# hdmi.net
KiCad netlist of a schematic drawn in Altium Designer
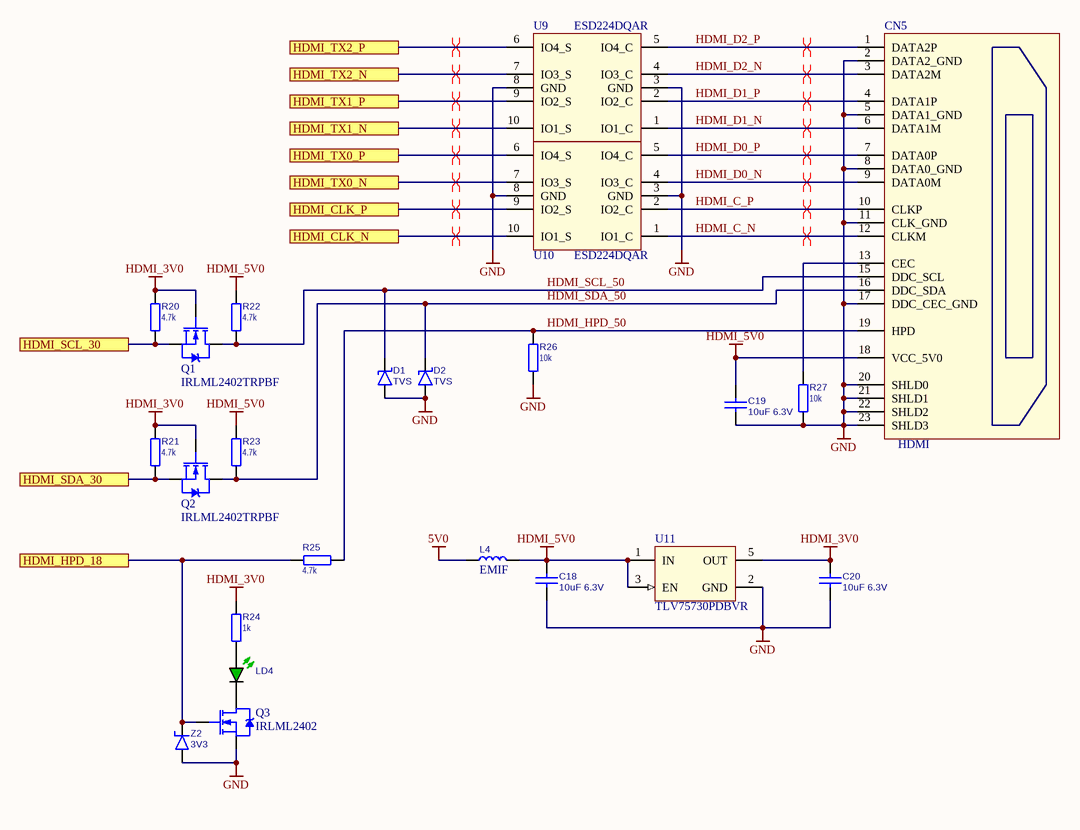
[diagram p0: hdmi.SchDoc]

(export (version "E")
  (design (tool "Eeschema 10.0.6"))
  (components
    (comp (ref "C18")
      (value "10uF 6.3V")
      (footprint "Capacitors:C0603")
      (description "CAP_NPOL")
      (fields (field (name "Comment") "CC0603MRX5R5BB106"))
      (libsource (lib "capacitors") (part "CAP_NPOL"))
    )
    (comp (ref "C19")
      (value "10uF 6.3V")
      (footprint "Capacitors:C0603")
      (description "CAP_NPOL")
      (fields (field (name "Comment") "CC0603MRX5R5BB106"))
      (libsource (lib "capacitors") (part "CAP_NPOL"))
    )
    (comp (ref "C20")
      (value "10uF 6.3V")
      (footprint "Capacitors:C0603")
      (description "CAP_NPOL")
      (fields (field (name "Comment") "CC0603MRX5R5BB106"))
      (libsource (lib "capacitors") (part "CAP_NPOL"))
    )
    (comp (ref "CN5")
      (value "HDMI")
      (footprint "1747981-1")
      (fields (field (name "Comment") "KLS1-285-19-22-N1B"))
      (libsource (lib "HDMI") (part "HDMI"))
    )
    (comp (ref "D1")
      (value "TVS")
      (footprint "SOD-323")
      (description "SHOTTKY")
      (fields (field (name "Comment") "CDSOD323-T05LC"))
      (libsource (lib "diodes") (part "SHOTTKY"))
    )
    (comp (ref "D2")
      (value "TVS")
      (footprint "SOD-323")
      (description "SHOTTKY")
      (fields (field (name "Comment") "CDSOD323-T05LC"))
      (libsource (lib "diodes") (part "SHOTTKY"))
    )
    (comp (ref "L4")
      (value "EMIF")
      (footprint "IND0805")
      (description "IND_WO_IRON")
      (fields (field (name "Comment") "BLM21PG221SN1D"))
      (libsource (lib "inductors") (part "IND_WO_IRON"))
    )
    (comp (ref "LD4")
      (value "LED_G")
      (footprint "LED0805")
      (description "LED Green")
      (libsource (lib "leds") (part "LED_GREEN"))
    )
    (comp (ref "Q1")
      (value "IRLML2402TRPBF")
      (footprint "SOT-23-3")
      (description "HEXFET Power MOSFET")
      (libsource (lib "MOSFET") (part "N-Channel"))
    )
    (comp (ref "Q2")
      (value "IRLML2402TRPBF")
      (footprint "SOT-23-3")
      (description "HEXFET Power MOSFET")
      (libsource (lib "MOSFET") (part "N-Channel"))
    )
    (comp (ref "Q3")
      (value "IRLML2402")
      (footprint "SOT-23-3")
      (description "HEXFET Power MOSFET")
      (libsource (lib "MOSFET") (part "N-Channel"))
    )
    (comp (ref "R20")
      (value "4.7k")
      (footprint "R0603")
      (description "RES")
      (libsource (lib "resistors") (part "RESISTOR"))
    )
    (comp (ref "R21")
      (value "4.7k")
      (footprint "R0603")
      (description "RES")
      (libsource (lib "resistors") (part "RESISTOR"))
    )
    (comp (ref "R22")
      (value "4.7k")
      (footprint "R0603")
      (description "RES")
      (libsource (lib "resistors") (part "RESISTOR"))
    )
    (comp (ref "R23")
      (value "4.7k")
      (footprint "R0603")
      (description "RES")
      (libsource (lib "resistors") (part "RESISTOR"))
    )
    (comp (ref "R24")
      (value "1k")
      (footprint "R0603")
      (description "RES")
      (libsource (lib "resistors") (part "RESISTOR"))
    )
    (comp (ref "R25")
      (value "4.7k")
      (footprint "R0603")
      (description "RES")
      (libsource (lib "resistors") (part "RESISTOR"))
    )
    (comp (ref "R26")
      (value "10k")
      (footprint "R0603")
      (description "RES")
      (libsource (lib "resistors") (part "RESISTOR"))
    )
    (comp (ref "R27")
      (value "10k")
      (footprint "R0603")
      (description "RES")
      (libsource (lib "resistors") (part "RESISTOR"))
    )
    (comp (ref "U9")
      (value "ESD224DQAR")
      (footprint "USON-10")
      (description "ESD224 Low Clamping 4-Channel ESD Protection Device for HDMI Interface")
      (libsource (lib "ESD") (part "ESD224"))
    )
    (comp (ref "U10")
      (value "ESD224DQAR")
      (footprint "USON-10")
      (description "ESD224 Low Clamping 4-Channel ESD Protection Device for HDMI Interface")
      (libsource (lib "ESD") (part "ESD224"))
    )
    (comp (ref "U11")
      (value "TLV75730PDBVR")
      (footprint "SOT-23-5")
      (description "Capacitor-Free, 300-mA, Low-Dropout Regulator with Foldback Current Limit for Portable Devices")
      (libsource (lib "TLV733P") (part "TLV733P"))
    )
    (comp (ref "Z2")
      (value "3V3")
      (footprint "SOD-80C")
      (description "ZENNER")
      (fields (field (name "Comment") "BZV55-C3V3.115"))
      (libsource (lib "diodes") (part "ZENNER_1"))
    )
  )
  (nets
    (net (code "1") (name "/HDMI_CLK_N") (class "Default")
      (node (ref "U10") (pin "10") (pinfunction "IO1_S_10") (pintype "passive"))
    )
    (net (code "2") (name "/HDMI_CLK_P") (class "Default")
      (node (ref "U10") (pin "9") (pinfunction "IO2_S_9") (pintype "passive"))
    )
    (net (code "3") (name "/HDMI_C_N") (class "Default")
      (node (ref "CN5") (pin "12") (pinfunction "CLKM_12") (pintype "passive"))
      (node (ref "U10") (pin "1") (pinfunction "IO1_C_1") (pintype "passive"))
    )
    (net (code "4") (name "/HDMI_C_P") (class "Default")
      (node (ref "CN5") (pin "10") (pinfunction "CLKP_10") (pintype "passive"))
      (node (ref "U10") (pin "2") (pinfunction "IO2_C_2") (pintype "passive"))
    )
    (net (code "5") (name "/HDMI_D0_N") (class "Default")
      (node (ref "CN5") (pin "9") (pinfunction "DATA0M_9") (pintype "passive"))
      (node (ref "U10") (pin "4") (pinfunction "IO3_C_4") (pintype "passive"))
    )
    (net (code "6") (name "/HDMI_D0_P") (class "Default")
      (node (ref "CN5") (pin "7") (pinfunction "DATA0P_7") (pintype "passive"))
      (node (ref "U10") (pin "5") (pinfunction "IO4_C_5") (pintype "passive"))
    )
    (net (code "7") (name "/HDMI_D1_N") (class "Default")
      (node (ref "CN5") (pin "6") (pinfunction "DATA1M_6") (pintype "passive"))
      (node (ref "U9") (pin "1") (pinfunction "IO1_C_1") (pintype "passive"))
    )
    (net (code "8") (name "/HDMI_D1_P") (class "Default")
      (node (ref "CN5") (pin "4") (pinfunction "DATA1P_4") (pintype "passive"))
      (node (ref "U9") (pin "2") (pinfunction "IO2_C_2") (pintype "passive"))
    )
    (net (code "9") (name "/HDMI_D2_N") (class "Default")
      (node (ref "CN5") (pin "3") (pinfunction "DATA2M_3") (pintype "passive"))
      (node (ref "U9") (pin "4") (pinfunction "IO3_C_4") (pintype "passive"))
    )
    (net (code "10") (name "/HDMI_D2_P") (class "Default")
      (node (ref "CN5") (pin "1") (pinfunction "DATA2P_1") (pintype "passive"))
      (node (ref "U9") (pin "5") (pinfunction "IO4_C_5") (pintype "passive"))
    )
    (net (code "11") (name "/HDMI_HPD_18") (class "Default")
      (node (ref "Q3") (pin "1") (pinfunction "G_1") (pintype "passive"))
      (node (ref "R25") (pin "1") (pinfunction "1_1") (pintype "passive"))
      (node (ref "Z2") (pin "2") (pinfunction "K_2") (pintype "passive"))
    )
    (net (code "12") (name "/HDMI_HPD_50") (class "Default")
      (node (ref "CN5") (pin "19") (pinfunction "HPD_19") (pintype "passive"))
      (node (ref "R25") (pin "2") (pinfunction "2_2") (pintype "passive"))
      (node (ref "R26") (pin "2") (pinfunction "2_2") (pintype "passive"))
    )
    (net (code "13") (name "/HDMI_SCL_30") (class "Default")
      (node (ref "Q1") (pin "2") (pinfunction "S_2") (pintype "passive"))
      (node (ref "R20") (pin "1") (pinfunction "1_1") (pintype "passive"))
    )
    (net (code "14") (name "/HDMI_SCL_50") (class "Default")
      (node (ref "CN5") (pin "15") (pinfunction "DDC_SCL_15") (pintype "passive"))
      (node (ref "D1") (pin "2") (pinfunction "K_2") (pintype "passive"))
      (node (ref "Q1") (pin "3") (pinfunction "D_3") (pintype "passive"))
      (node (ref "R22") (pin "1") (pinfunction "1_1") (pintype "passive"))
    )
    (net (code "15") (name "/HDMI_SDA_30") (class "Default")
      (node (ref "Q2") (pin "2") (pinfunction "S_2") (pintype "passive"))
      (node (ref "R21") (pin "1") (pinfunction "1_1") (pintype "passive"))
    )
    (net (code "16") (name "/HDMI_SDA_50") (class "Default")
      (node (ref "CN5") (pin "16") (pinfunction "DDC_SDA_16") (pintype "passive"))
      (node (ref "D2") (pin "2") (pinfunction "K_2") (pintype "passive"))
      (node (ref "Q2") (pin "3") (pinfunction "D_3") (pintype "passive"))
      (node (ref "R23") (pin "1") (pinfunction "1_1") (pintype "passive"))
    )
    (net (code "17") (name "/HDMI_TX0_N") (class "Default")
      (node (ref "U10") (pin "7") (pinfunction "IO3_S_7") (pintype "passive"))
    )
    (net (code "18") (name "/HDMI_TX0_P") (class "Default")
      (node (ref "U10") (pin "6") (pinfunction "IO4_S_6") (pintype "passive"))
    )
    (net (code "19") (name "/HDMI_TX1_N") (class "Default")
      (node (ref "U9") (pin "10") (pinfunction "IO1_S_10") (pintype "passive"))
    )
    (net (code "20") (name "/HDMI_TX1_P") (class "Default")
      (node (ref "U9") (pin "9") (pinfunction "IO2_S_9") (pintype "passive"))
    )
    (net (code "21") (name "/HDMI_TX2_N") (class "Default")
      (node (ref "U9") (pin "7") (pinfunction "IO3_S_7") (pintype "passive"))
    )
    (net (code "22") (name "/HDMI_TX2_P") (class "Default")
      (node (ref "U9") (pin "6") (pinfunction "IO4_S_6") (pintype "passive"))
    )
    (net (code "23") (name "5V0") (class "Default") (node (ref "L4") (pin "2") (pintype "passive")))
    (net (code "24") (name "GND") (class "Default")
      (node (ref "C18") (pin "2") (pinfunction "2_2") (pintype "passive"))
      (node (ref "C19") (pin "2") (pinfunction "2_2") (pintype "passive"))
      (node (ref "C20") (pin "2") (pinfunction "2_2") (pintype "passive"))
      (node (ref "CN5") (pin "11") (pinfunction "CLK_GND_11") (pintype "passive"))
      (node (ref "CN5") (pin "17") (pinfunction "DDC_CEC_GND_17") (pintype "passive"))
      (node (ref "CN5") (pin "2") (pinfunction "DATA2_GND_2") (pintype "passive"))
      (node (ref "CN5") (pin "20") (pinfunction "SHLD0_20") (pintype "passive"))
      (node (ref "CN5") (pin "21") (pinfunction "SHLD1_21") (pintype "passive"))
      (node (ref "CN5") (pin "22") (pinfunction "SHLD2_22") (pintype "passive"))
      (node (ref "CN5") (pin "23") (pinfunction "SHLD3_23") (pintype "passive"))
      (node (ref "CN5") (pin "5") (pinfunction "DATA1_GND_5") (pintype "passive"))
      (node (ref "CN5") (pin "8") (pinfunction "DATA0_GND_8") (pintype "passive"))
      (node (ref "D1") (pin "1") (pinfunction "A_1") (pintype "passive"))
      (node (ref "D2") (pin "1") (pinfunction "A_1") (pintype "passive"))
      (node (ref "Q3") (pin "2") (pinfunction "S_2") (pintype "passive"))
      (node (ref "R26") (pin "1") (pinfunction "1_1") (pintype "passive"))
      (node (ref "R27") (pin "1") (pinfunction "1_1") (pintype "passive"))
      (node (ref "U10") (pin "3") (pinfunction "GND_3") (pintype "passive"))
      (node (ref "U10") (pin "8") (pinfunction "GND_8") (pintype "passive"))
      (node (ref "U11") (pin "2") (pinfunction "GND_2") (pintype "power_in"))
      (node (ref "U9") (pin "3") (pinfunction "GND_3") (pintype "passive"))
      (node (ref "U9") (pin "8") (pinfunction "GND_8") (pintype "passive"))
      (node (ref "Z2") (pin "1") (pinfunction "A_1") (pintype "passive"))
    )
    (net (code "25") (name "HDMI_3V0") (class "Default")
      (node (ref "C20") (pin "1") (pinfunction "1_1") (pintype "passive"))
      (node (ref "Q1") (pin "1") (pinfunction "G_1") (pintype "passive"))
      (node (ref "Q2") (pin "1") (pinfunction "G_1") (pintype "passive"))
      (node (ref "R20") (pin "2") (pinfunction "2_2") (pintype "passive"))
      (node (ref "R21") (pin "2") (pinfunction "2_2") (pintype "passive"))
      (node (ref "R24") (pin "2") (pinfunction "2_2") (pintype "passive"))
      (node (ref "U11") (pin "5") (pinfunction "OUT_5") (pintype "power_in"))
    )
    (net (code "26") (name "HDMI_5V0") (class "Default")
      (node (ref "C18") (pin "1") (pinfunction "1_1") (pintype "passive"))
      (node (ref "C19") (pin "1") (pinfunction "1_1") (pintype "passive"))
      (node (ref "CN5") (pin "18") (pinfunction "VCC_5V0_18") (pintype "passive"))
      (node (ref "L4") (pin "1") (pintype "passive"))
      (node (ref "R22") (pin "2") (pinfunction "2_2") (pintype "passive"))
      (node (ref "R23") (pin "2") (pinfunction "2_2") (pintype "passive"))
      (node (ref "U11") (pin "1") (pinfunction "IN_1") (pintype "power_in"))
      (node (ref "U11") (pin "3") (pinfunction "EN_3") (pintype "input"))
    )
    (net (code "27") (name "Net-(CN5-CEC)") (class "Default")
      (node (ref "CN5") (pin "13") (pinfunction "CEC_13") (pintype "passive"))
      (node (ref "R27") (pin "2") (pinfunction "2_2") (pintype "passive"))
    )
    (net (code "28") (name "Net-(LD4-Pad2)") (class "Default")
      (node (ref "LD4") (pin "2") (pintype "passive"))
      (node (ref "R24") (pin "1") (pinfunction "1_1") (pintype "passive"))
    )
    (net (code "29") (name "Net-(Q3-D)") (class "Default")
      (node (ref "LD4") (pin "1") (pintype "passive"))
      (node (ref "Q3") (pin "3") (pinfunction "D_3") (pintype "passive"))
    )
  )
)
